# SparkFun_STM32_Thing_Plus.net
KiCad netlist of a schematic drawn in EAGLE
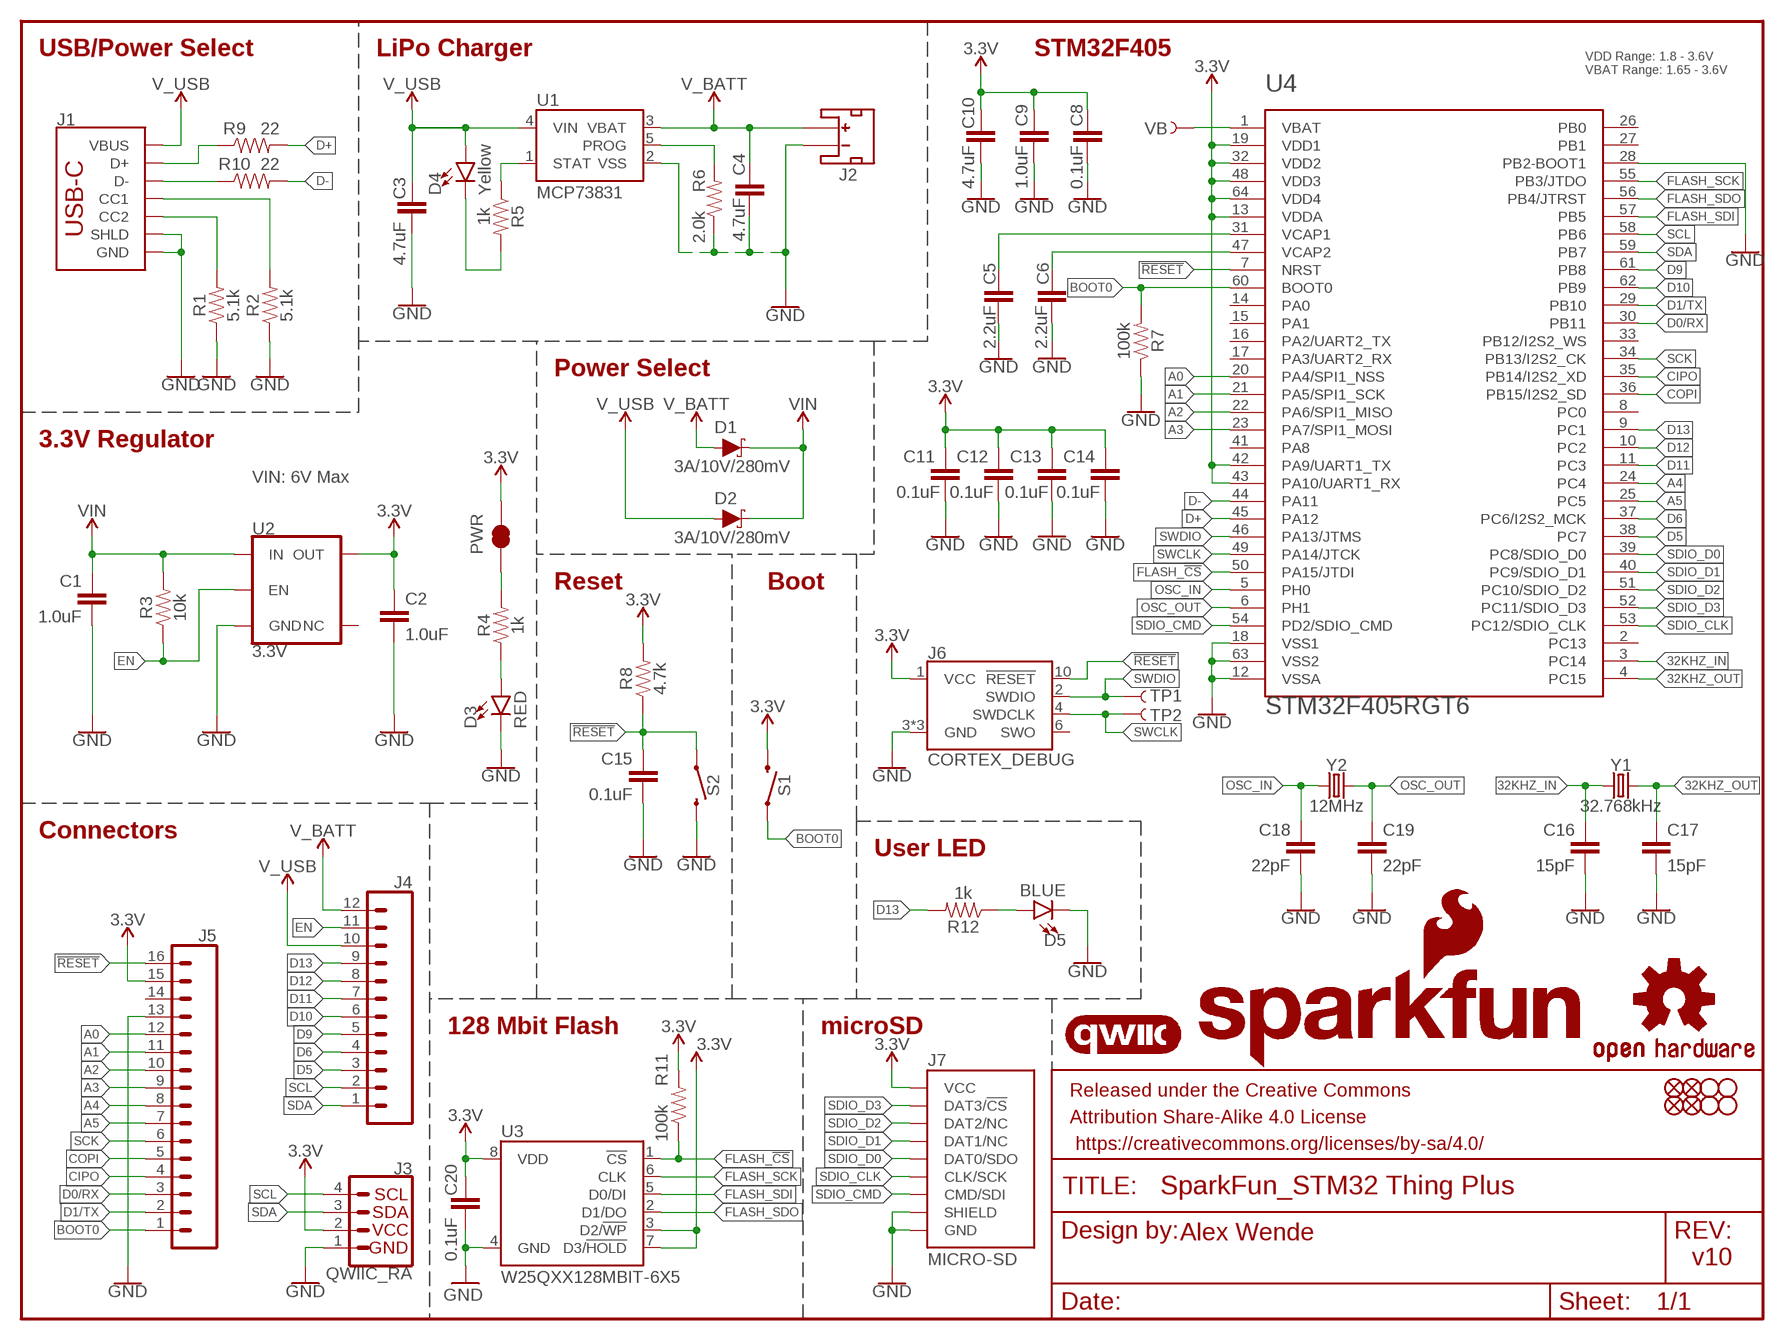
[diagram p0: schematic, sheet 1]

(export (version "E")
  (design (tool "Eeschema 10.0.6"))
  (components
    (comp (ref "C1")
      (value "1.0uF")
      (footprint "eagle-import:0402-TIGHT")
      (libsource (lib "eagle-import") (part "1.0UF-0402T-16V-10%"))
    )
    (comp (ref "C2")
      (value "1.0uF")
      (footprint "eagle-import:0402-TIGHT")
      (libsource (lib "eagle-import") (part "1.0UF-0402T-16V-10%"))
    )
    (comp (ref "C3")
      (value "4.7uF")
      (footprint "eagle-import:0402-TIGHT")
      (libsource (lib "eagle-import") (part "4.7UF-0402_TIGHT-6.3V-20%-X5R"))
    )
    (comp (ref "C4")
      (value "4.7uF")
      (footprint "eagle-import:0402-TIGHT")
      (libsource (lib "eagle-import") (part "4.7UF-0402_TIGHT-6.3V-20%-X5R"))
    )
    (comp (ref "C5")
      (value "2.2uF")
      (footprint "eagle-import:0402-TIGHT")
      (libsource (lib "eagle-import") (part "2.2UF-0402_TIGHT-10V-10%-X5R"))
    )
    (comp (ref "C6")
      (value "2.2uF")
      (footprint "eagle-import:0402-TIGHT")
      (libsource (lib "eagle-import") (part "2.2UF-0402_TIGHT-10V-10%-X5R"))
    )
    (comp (ref "C8")
      (value "0.1uF")
      (footprint "eagle-import:0402-TIGHT")
      (libsource (lib "eagle-import") (part "0.1UF-0402T-10V-10%-X7R"))
    )
    (comp (ref "C9")
      (value "1.0uF")
      (footprint "eagle-import:0402-TIGHT")
      (libsource (lib "eagle-import") (part "1.0UF-0402T-16V-10%"))
    )
    (comp (ref "C10")
      (value "4.7uF")
      (footprint "eagle-import:0402-TIGHT")
      (libsource (lib "eagle-import") (part "4.7UF-0402_TIGHT-6.3V-20%-X5R"))
    )
    (comp (ref "C11")
      (value "0.1uF")
      (footprint "eagle-import:0402-TIGHT")
      (libsource (lib "eagle-import") (part "0.1UF-0402T-10V-10%-X7R"))
    )
    (comp (ref "C12")
      (value "0.1uF")
      (footprint "eagle-import:0402-TIGHT")
      (libsource (lib "eagle-import") (part "0.1UF-0402T-10V-10%-X7R"))
    )
    (comp (ref "C13")
      (value "0.1uF")
      (footprint "eagle-import:0402-TIGHT")
      (libsource (lib "eagle-import") (part "0.1UF-0402T-10V-10%-X7R"))
    )
    (comp (ref "C14")
      (value "0.1uF")
      (footprint "eagle-import:0402-TIGHT")
      (libsource (lib "eagle-import") (part "0.1UF-0402T-10V-10%-X7R"))
    )
    (comp (ref "C15")
      (value "0.1uF")
      (footprint "eagle-import:0402-TIGHT")
      (libsource (lib "eagle-import") (part "0.1UF-0402T-10V-10%-X7R"))
    )
    (comp (ref "C16")
      (value "15pF")
      (footprint "eagle-import:0402-TIGHT")
      (libsource (lib "eagle-import") (part "15PF-0402T-50V-5%"))
    )
    (comp (ref "C17")
      (value "15pF")
      (footprint "eagle-import:0402-TIGHT")
      (libsource (lib "eagle-import") (part "15PF-0402T-50V-5%"))
    )
    (comp (ref "C18")
      (value "22pF")
      (footprint "eagle-import:0402-TIGHT")
      (libsource (lib "eagle-import") (part "22PF-0402T-16V-10%"))
    )
    (comp (ref "C19")
      (value "22pF")
      (footprint "eagle-import:0402-TIGHT")
      (libsource (lib "eagle-import") (part "22PF-0402T-16V-10%"))
    )
    (comp (ref "C20")
      (value "0.1uF")
      (footprint "eagle-import:0402-TIGHT")
      (libsource (lib "eagle-import") (part "0.1UF-0402T-10V-10%-X7R"))
    )
    (comp (ref "D1")
      (value "3A/10V/280mV")
      (footprint "eagle-import:SOD-323")
      (libsource (lib "eagle-import") (part "DIODE-SCHOTTKY-BAT60A"))
    )
    (comp (ref "D2")
      (value "3A/10V/280mV")
      (footprint "eagle-import:SOD-323")
      (libsource (lib "eagle-import") (part "DIODE-SCHOTTKY-BAT60A"))
    )
    (comp (ref "D3")
      (value "RED")
      (footprint "eagle-import:LED-0603")
      (libsource (lib "eagle-import") (part "LED-RED0603"))
    )
    (comp (ref "D4")
      (value "Yellow")
      (footprint "eagle-import:LED-0603")
      (libsource (lib "eagle-import") (part "LED-YELLOW0603"))
    )
    (comp (ref "D5")
      (value "BLUE")
      (footprint "eagle-import:LED-0603")
      (libsource (lib "eagle-import") (part "LED-BLUE0603"))
    )
    (comp (ref "FD1")
      (value "FIDUCIALUFIDUCIAL")
      (footprint "eagle-import:FIDUCIAL-MICRO")
      (libsource (lib "eagle-import") (part "FIDUCIALUFIDUCIAL"))
    )
    (comp (ref "FD2")
      (value "FIDUCIALUFIDUCIAL")
      (footprint "eagle-import:FIDUCIAL-MICRO")
      (libsource (lib "eagle-import") (part "FIDUCIALUFIDUCIAL"))
    )
    (comp (ref "FD3")
      (value "FIDUCIALUFIDUCIAL")
      (footprint "eagle-import:FIDUCIAL-MICRO")
      (libsource (lib "eagle-import") (part "FIDUCIALUFIDUCIAL"))
    )
    (comp (ref "FD4")
      (value "FIDUCIALUFIDUCIAL")
      (footprint "eagle-import:FIDUCIAL-MICRO")
      (libsource (lib "eagle-import") (part "FIDUCIALUFIDUCIAL"))
    )
    (comp (ref "FRAME1")
      (value "FRAME-LETTER")
      (footprint "eagle-import:CREATIVE_COMMONS")
      (libsource (lib "eagle-import") (part "FRAME-LETTER"))
    )
    (comp (ref "H1")
      (value "STAND-OFFTIGHT")
      (footprint "eagle-import:STAND-OFF-TIGHT")
      (libsource (lib "eagle-import") (part "STAND-OFFTIGHT"))
    )
    (comp (ref "H2")
      (value "STAND-OFFTIGHT")
      (footprint "eagle-import:STAND-OFF-TIGHT")
      (libsource (lib "eagle-import") (part "STAND-OFFTIGHT"))
    )
    (comp (ref "H3")
      (value "STAND-OFFTIGHT")
      (footprint "eagle-import:STAND-OFF-TIGHT")
      (libsource (lib "eagle-import") (part "STAND-OFFTIGHT"))
    )
    (comp (ref "H4")
      (value "STAND-OFFTIGHT")
      (footprint "eagle-import:STAND-OFF-TIGHT")
      (libsource (lib "eagle-import") (part "STAND-OFFTIGHT"))
    )
    (comp (ref "J1")
      (value "USB_C_2-LAYER_PADS")
      (footprint "eagle-import:USB-C-16P-2LAYER-PADS")
      (libsource (lib "eagle-import") (part "USB_C_2-LAYER_PADS"))
    )
    (comp (ref "J2")
      (value "JST_2MM_MALE")
      (footprint "eagle-import:JST-2-SMD")
      (libsource (lib "eagle-import") (part "JST_2MM_MALE"))
    )
    (comp (ref "J3")
      (value "QWIIC_RA")
      (footprint "eagle-import:JST04_1MM_RA")
      (libsource (lib "eagle-import") (part "QWIIC_CONNECTORJS-1MM"))
    )
    (comp (ref "J4")
      (value "CONN_12SM_SQ_NO_SILK")
      (footprint "eagle-import:1X12_SM_SQ_NOSILK")
      (libsource (lib "eagle-import") (part "CONN_12SM_SQ_NO_SILK"))
    )
    (comp (ref "J5")
      (value "CONN_161X16_SM_SQ_NOSILK")
      (footprint "eagle-import:1X16_SM_SQ_NOSILK")
      (libsource (lib "eagle-import") (part "CONN_161X16_SM_SQ_NOSILK"))
    )
    (comp (ref "J6")
      (value "CORTEX_DEBUG")
      (footprint "eagle-import:2X5-PTH-1.27MM-NO_SILK")
      (libsource (lib "eagle-import") (part "CORTEX_JTAG_DEBUG_MINIMUM_PTH_NS"))
    )
    (comp (ref "J7")
      (value "MICRO-SD")
      (footprint "eagle-import:MICRO-SD-SOCKET")
      (libsource (lib "eagle-import") (part "MICRO-SD-SDIOPUSH-PUSH"))
    )
    (comp (ref "LOGO1")
      (value "QWIIC_LOGO_5MM")
      (footprint "eagle-import:QWIIC_5MM")
      (libsource (lib "eagle-import") (part "QWIIC_LOGO_5MM"))
    )
    (comp (ref "LOGO2")
      (value "SFE_LOGO_NAME_FLAME.1_INCH")
      (footprint "eagle-import:SFE_LOGO_NAME_FLAME_.1")
      (libsource (lib "eagle-import") (part "SFE_LOGO_NAME_FLAME.1_INCH"))
    )
    (comp (ref "LOGO3")
      (value "OSHW-LOGOS")
      (footprint "eagle-import:OSHW-LOGO-S")
      (libsource (lib "eagle-import") (part "OSHW-LOGOS"))
    )
    (comp (ref "PWR")
      (value "JUMPER-SMT_2_NC_TRACE_NO-SILK")
      (footprint "eagle-import:SMT-JUMPER_2_NC_TRACE_NO-SILK")
      (libsource (lib "eagle-import") (part "JUMPER-SMT_2_NC_TRACE_NO-SILK"))
    )
    (comp (ref "R1")
      (value "5.1k")
      (footprint "eagle-import:0603")
      (libsource (lib "eagle-import") (part "5.1KOHM5.1KOHM-0603-1/10W-1%"))
    )
    (comp (ref "R2")
      (value "5.1k")
      (footprint "eagle-import:0603")
      (libsource (lib "eagle-import") (part "5.1KOHM5.1KOHM-0603-1/10W-1%"))
    )
    (comp (ref "R3")
      (value "10k")
      (footprint "eagle-import:0603")
      (libsource (lib "eagle-import") (part "10KOHM-0603-1/10W-1%"))
    )
    (comp (ref "R4")
      (value "1k")
      (footprint "eagle-import:0402-TIGHT")
      (libsource (lib "eagle-import") (part "1KOHM-0402T-1/16W-1%"))
    )
    (comp (ref "R5")
      (value "1k")
      (footprint "eagle-import:0402-TIGHT")
      (libsource (lib "eagle-import") (part "1KOHM-0402T-1/16W-1%"))
    )
    (comp (ref "R6")
      (value "2.0k")
      (footprint "eagle-import:0603")
      (libsource (lib "eagle-import") (part "2.0KOHM-0603-1/10W-5%"))
    )
    (comp (ref "R7")
      (value "100k")
      (footprint "eagle-import:0402-TIGHT")
      (libsource (lib "eagle-import") (part "100KOHM-0402T-1/16W-1%"))
    )
    (comp (ref "R8")
      (value "4.7k")
      (footprint "eagle-import:0603")
      (libsource (lib "eagle-import") (part "4.7KOHM-0603-1/10W-1%"))
    )
    (comp (ref "R9")
      (value "22")
      (footprint "eagle-import:0603")
      (libsource (lib "eagle-import") (part "22OHM-0603-1/10W-1%"))
    )
    (comp (ref "R10")
      (value "22")
      (footprint "eagle-import:0603")
      (libsource (lib "eagle-import") (part "22OHM-0603-1/10W-1%"))
    )
    (comp (ref "R11")
      (value "100k")
      (footprint "eagle-import:0402-TIGHT")
      (libsource (lib "eagle-import") (part "100KOHM-0402T-1/16W-1%"))
    )
    (comp (ref "R12")
      (value "1k")
      (footprint "eagle-import:0402-TIGHT")
      (libsource (lib "eagle-import") (part "1KOHM-0402T-1/16W-1%"))
    )
    (comp (ref "S1")
      (value "MOMENTARY-SWITCH-SPST-SMD-4.6X2.8MM")
      (footprint "eagle-import:TACTILE_SWITCH_SMD_4.6X2.8MM")
      (libsource (lib "eagle-import") (part "MOMENTARY-SWITCH-SPST-SMD-4.6X2.8MM"))
    )
    (comp (ref "S2")
      (value "MOMENTARY-SWITCH-SPST-SMD-4.6X2.8MM")
      (footprint "eagle-import:TACTILE_SWITCH_SMD_4.6X2.8MM")
      (libsource (lib "eagle-import") (part "MOMENTARY-SWITCH-SPST-SMD-4.6X2.8MM"))
    )
    (comp (ref "TP1")
      (value "TEST-POINT3")
      (footprint "eagle-import:PAD.03X.03")
      (libsource (lib "eagle-import") (part "TEST-POINT3"))
    )
    (comp (ref "TP2")
      (value "TEST-POINT3")
      (footprint "eagle-import:PAD.03X.03")
      (libsource (lib "eagle-import") (part "TEST-POINT3"))
    )
    (comp (ref "U1")
      (value "MCP73831")
      (footprint "eagle-import:SOT23-5")
      (libsource (lib "eagle-import") (part "MCP73831"))
    )
    (comp (ref "U2")
      (value "3.3V")
      (footprint "eagle-import:SOT23-5")
      (libsource (lib "eagle-import") (part "V_REG_AP2112K-3.3V"))
    )
    (comp (ref "U3")
      (value "W25QXX128MBIT-6X5")
      (footprint "eagle-import:WSON-8-6X5")
      (libsource (lib "eagle-import") (part "W25QXX128MBIT-6X5"))
    )
    (comp (ref "U4")
      (value "STM32F405RGT6")
      (footprint "eagle-import:TQFP64")
      (libsource (lib "eagle-import") (part "STM32F405RG"))
    )
    (comp (ref "VB")
      (value "TEST-POINT3")
      (footprint "eagle-import:PAD.03X.03")
      (libsource (lib "eagle-import") (part "TEST-POINT3"))
    )
    (comp (ref "Y1")
      (value "32.768kHz")
      (footprint "eagle-import:CRYSTAL-SMD-3.2X1.5MM")
      (libsource (lib "eagle-import") (part "CRYSTAL-32.768KHZSMD-3.2X1.5"))
    )
    (comp (ref "Y2")
      (value "12MHz")
      (footprint "eagle-import:CRYSTAL-SMD-5X3.2-4PAD")
      (libsource (lib "eagle-import") (part "CRYSTAL-12MHZ{dblquote}"))
    )
  )
  (nets
    (net (code "1") (name "/FLASH_~{CS}") (class "Default")
      (node (ref "R11") (pin "1") (pinfunction "1_1") (pintype "passive"))
      (node (ref "U3") (pin "1") (pinfunction "~{CS}_1") (pintype "bidirectional"))
      (node (ref "U4") (pin "50") (pinfunction "PA15/JTDI_50") (pintype "bidirectional"))
    )
    (net (code "2") (name "/~{RESET}") (class "Default")
      (node (ref "C15") (pin "1") (pinfunction "1_1") (pintype "passive"))
      (node (ref "J5") (pin "16") (pinfunction "16_16") (pintype "passive"))
      (node (ref "J6") (pin "10") (pinfunction "~{RESET}_10") (pintype "bidirectional"))
      (node (ref "R8") (pin "1") (pinfunction "1_1") (pintype "passive"))
      (node (ref "S2") (pin "1") (pinfunction "1_1") (pintype "passive"))
      (node (ref "S2") (pin "2") (pinfunction "1_2") (pintype "passive"))
      (node (ref "U4") (pin "7") (pinfunction "NRST_7") (pintype "bidirectional"))
    )
    (net (code "3") (name "3.3V") (class "Default")
      (node (ref "C10") (pin "1") (pinfunction "1_1") (pintype "passive"))
      (node (ref "C11") (pin "1") (pinfunction "1_1") (pintype "passive"))
      (node (ref "C12") (pin "1") (pinfunction "1_1") (pintype "passive"))
      (node (ref "C13") (pin "1") (pinfunction "1_1") (pintype "passive"))
      (node (ref "C14") (pin "1") (pinfunction "1_1") (pintype "passive"))
      (node (ref "C2") (pin "1") (pinfunction "1_1") (pintype "passive"))
      (node (ref "C20") (pin "1") (pinfunction "1_1") (pintype "passive"))
      (node (ref "C8") (pin "1") (pinfunction "1_1") (pintype "passive"))
      (node (ref "C9") (pin "1") (pinfunction "1_1") (pintype "passive"))
      (node (ref "J3") (pin "2") (pinfunction "2_2") (pintype "power_in"))
      (node (ref "J5") (pin "15") (pinfunction "15_15") (pintype "passive"))
      (node (ref "J6") (pin "1") (pinfunction "VCC_1") (pintype "bidirectional"))
      (node (ref "J7") (pin "VCC") (pinfunction "VCC_VCC") (pintype "bidirectional"))
      (node (ref "PWR") (pin "2") (pinfunction "2_2") (pintype "passive"))
      (node (ref "R11") (pin "2") (pinfunction "2_2") (pintype "passive"))
      (node (ref "R8") (pin "2") (pinfunction "2_2") (pintype "passive"))
      (node (ref "S1") (pin "3") (pinfunction "2_3") (pintype "passive"))
      (node (ref "S1") (pin "4") (pinfunction "2_4") (pintype "passive"))
      (node (ref "U2") (pin "5") (pinfunction "OUT_5") (pintype "passive"))
      (node (ref "U3") (pin "3") (pinfunction "D2/~{WP}_3") (pintype "bidirectional"))
      (node (ref "U3") (pin "7") (pinfunction "D3/~{HOLD}_7") (pintype "bidirectional"))
      (node (ref "U3") (pin "8") (pinfunction "VDD_8") (pintype "bidirectional"))
      (node (ref "U4") (pin "13") (pinfunction "VDDA_13") (pintype "bidirectional"))
      (node (ref "U4") (pin "19") (pinfunction "VDD1_19") (pintype "bidirectional"))
      (node (ref "U4") (pin "32") (pinfunction "VDD2_32") (pintype "bidirectional"))
      (node (ref "U4") (pin "42") (pinfunction "PA9/UART1_TX_42") (pintype "bidirectional"))
      (node (ref "U4") (pin "43") (pinfunction "PA10/UART1_RX_43") (pintype "bidirectional"))
      (node (ref "U4") (pin "48") (pinfunction "VDD3_48") (pintype "bidirectional"))
      (node (ref "U4") (pin "64") (pinfunction "VDD4_64") (pintype "bidirectional"))
    )
    (net (code "4") (name "32KHZ_IN") (class "Default")
      (node (ref "C16") (pin "1") (pinfunction "1_1") (pintype "passive"))
      (node (ref "U4") (pin "3") (pinfunction "PC14_3") (pintype "bidirectional"))
      (node (ref "Y1") (pin "P$1") (pinfunction "1_P$1") (pintype "passive"))
    )
    (net (code "5") (name "32KHZ_OUT") (class "Default")
      (node (ref "C17") (pin "1") (pinfunction "1_1") (pintype "passive"))
      (node (ref "U4") (pin "4") (pinfunction "PC15_4") (pintype "bidirectional"))
      (node (ref "Y1") (pin "P$2") (pinfunction "2_P$2") (pintype "passive"))
    )
    (net (code "6") (name "A0") (class "Default")
      (node (ref "J5") (pin "12") (pinfunction "12_12") (pintype "passive"))
      (node (ref "U4") (pin "20") (pinfunction "PA4/SPI1_NSS_20") (pintype "bidirectional"))
    )
    (net (code "7") (name "A1") (class "Default")
      (node (ref "J5") (pin "11") (pinfunction "11_11") (pintype "passive"))
      (node (ref "U4") (pin "21") (pinfunction "PA5/SPI1_SCK_21") (pintype "bidirectional"))
    )
    (net (code "8") (name "A2") (class "Default")
      (node (ref "J5") (pin "10") (pinfunction "10_10") (pintype "passive"))
      (node (ref "U4") (pin "22") (pinfunction "PA6/SPI1_MISO_22") (pintype "bidirectional"))
    )
    (net (code "9") (name "A3") (class "Default")
      (node (ref "J5") (pin "9") (pinfunction "9_9") (pintype "passive"))
      (node (ref "U4") (pin "23") (pinfunction "PA7/SPI1_MOSI_23") (pintype "bidirectional"))
    )
    (net (code "10") (name "A4") (class "Default")
      (node (ref "J5") (pin "8") (pinfunction "8_8") (pintype "passive"))
      (node (ref "U4") (pin "24") (pinfunction "PC4_24") (pintype "bidirectional"))
    )
    (net (code "11") (name "A5") (class "Default")
      (node (ref "J5") (pin "7") (pinfunction "7_7") (pintype "passive"))
      (node (ref "U4") (pin "25") (pinfunction "PC5_25") (pintype "bidirectional"))
    )
    (net (code "12") (name "BOOT0") (class "Default")
      (node (ref "J5") (pin "1") (pinfunction "1_1") (pintype "passive"))
      (node (ref "R7") (pin "2") (pinfunction "2_2") (pintype "passive"))
      (node (ref "S1") (pin "1") (pinfunction "1_1") (pintype "passive"))
      (node (ref "S1") (pin "2") (pinfunction "1_2") (pintype "passive"))
      (node (ref "U4") (pin "60") (pinfunction "BOOT0_60") (pintype "bidirectional"))
    )
    (net (code "13") (name "CIPO") (class "Default")
      (node (ref "J5") (pin "4") (pinfunction "4_4") (pintype "passive"))
      (node (ref "U4") (pin "35") (pinfunction "PB14/I2S2_XD_35") (pintype "bidirectional"))
    )
    (net (code "14") (name "COPI") (class "Default")
      (node (ref "J5") (pin "5") (pinfunction "5_5") (pintype "passive"))
      (node (ref "U4") (pin "36") (pinfunction "PB15/I2S2_SD_36") (pintype "bidirectional"))
    )
    (net (code "15") (name "D+") (class "Default")
      (node (ref "R9") (pin "2") (pinfunction "2_2") (pintype "passive"))
      (node (ref "U4") (pin "45") (pinfunction "PA12_45") (pintype "bidirectional"))
    )
    (net (code "16") (name "D-") (class "Default")
      (node (ref "R10") (pin "2") (pinfunction "2_2") (pintype "passive"))
      (node (ref "U4") (pin "44") (pinfunction "PA11_44") (pintype "bidirectional"))
    )
    (net (code "17") (name "D0{slash}RX") (class "Default")
      (node (ref "J5") (pin "3") (pinfunction "3_3") (pintype "passive"))
      (node (ref "U4") (pin "30") (pinfunction "PB11_30") (pintype "bidirectional"))
    )
    (net (code "18") (name "D1{slash}TX") (class "Default")
      (node (ref "J5") (pin "2") (pinfunction "2_2") (pintype "passive"))
      (node (ref "U4") (pin "29") (pinfunction "PB10_29") (pintype "bidirectional"))
    )
    (net (code "19") (name "D5") (class "Default")
      (node (ref "J4") (pin "3") (pinfunction "3_3") (pintype "passive"))
      (node (ref "U4") (pin "38") (pinfunction "PC7_38") (pintype "bidirectional"))
    )
    (net (code "20") (name "D6") (class "Default")
      (node (ref "J4") (pin "4") (pinfunction "4_4") (pintype "passive"))
      (node (ref "U4") (pin "37") (pinfunction "PC6/I2S2_MCK_37") (pintype "bidirectional"))
    )
    (net (code "21") (name "D9") (class "Default")
      (node (ref "J4") (pin "5") (pinfunction "5_5") (pintype "passive"))
      (node (ref "U4") (pin "61") (pinfunction "PB8_61") (pintype "bidirectional"))
    )
    (net (code "22") (name "D10") (class "Default")
      (node (ref "J4") (pin "6") (pinfunction "6_6") (pintype "passive"))
      (node (ref "U4") (pin "62") (pinfunction "PB9_62") (pintype "bidirectional"))
    )
    (net (code "23") (name "D11") (class "Default")
      (node (ref "J4") (pin "7") (pinfunction "7_7") (pintype "passive"))
      (node (ref "U4") (pin "11") (pinfunction "PC3_11") (pintype "bidirectional"))
    )
    (net (code "24") (name "D12") (class "Default")
      (node (ref "J4") (pin "8") (pinfunction "8_8") (pintype "passive"))
      (node (ref "U4") (pin "10") (pinfunction "PC2_10") (pintype "bidirectional"))
    )
    (net (code "25") (name "D13") (class "Default")
      (node (ref "J4") (pin "9") (pinfunction "9_9") (pintype "passive"))
      (node (ref "R12") (pin "2") (pinfunction "2_2") (pintype "passive"))
      (node (ref "U4") (pin "9") (pinfunction "PC1_9") (pintype "bidirectional"))
    )
    (net (code "26") (name "EN") (class "Default")
      (node (ref "J4") (pin "11") (pinfunction "11_11") (pintype "passive"))
      (node (ref "R3") (pin "1") (pinfunction "1_1") (pintype "passive"))
      (node (ref "U2") (pin "3") (pinfunction "EN_3") (pintype "input"))
    )
    (net (code "27") (name "FLASH_SCK") (class "Default")
      (node (ref "U3") (pin "6") (pinfunction "CLK_6") (pintype "bidirectional"))
      (node (ref "U4") (pin "55") (pinfunction "PB3/JTDO_55") (pintype "bidirectional"))
    )
    (net (code "28") (name "FLASH_SDI") (class "Default")
      (node (ref "U3") (pin "5") (pinfunction "D0/DI_5") (pintype "bidirectional"))
      (node (ref "U4") (pin "57") (pinfunction "PB5_57") (pintype "bidirectional"))
    )
    (net (code "29") (name "FLASH_SDO") (class "Default")
      (node (ref "U3") (pin "2") (pinfunction "D1/DO_2") (pintype "bidirectional"))
      (node (ref "U4") (pin "56") (pinfunction "PB4/JTRST_56") (pintype "bidirectional"))
    )
    (net (code "30") (name "GND") (class "Default")
      (node (ref "C1") (pin "2") (pinfunction "2_2") (pintype "passive"))
      (node (ref "C10") (pin "2") (pinfunction "2_2") (pintype "passive"))
      (node (ref "C11") (pin "2") (pinfunction "2_2") (pintype "passive"))
      (node (ref "C12") (pin "2") (pinfunction "2_2") (pintype "passive"))
      (node (ref "C13") (pin "2") (pinfunction "2_2") (pintype "passive"))
      (node (ref "C14") (pin "2") (pinfunction "2_2") (pintype "passive"))
      (node (ref "C15") (pin "2") (pinfunction "2_2") (pintype "passive"))
      (node (ref "C16") (pin "2") (pinfunction "2_2") (pintype "passive"))
      (node (ref "C17") (pin "2") (pinfunction "2_2") (pintype "passive"))
      (node (ref "C18") (pin "2") (pinfunction "2_2") (pintype "passive"))
      (node (ref "C19") (pin "2") (pinfunction "2_2") (pintype "passive"))
      (node (ref "C2") (pin "2") (pinfunction "2_2") (pintype "passive"))
      (node (ref "C20") (pin "2") (pinfunction "2_2") (pintype "passive"))
      (node (ref "C3") (pin "2") (pinfunction "2_2") (pintype "passive"))
      (node (ref "C4") (pin "2") (pinfunction "2_2") (pintype "passive"))
      (node (ref "C5") (pin "2") (pinfunction "2_2") (pintype "passive"))
      (node (ref "C6") (pin "2") (pinfunction "2_2") (pintype "passive"))
      (node (ref "C8") (pin "2") (pinfunction "2_2") (pintype "passive"))
      (node (ref "C9") (pin "2") (pinfunction "2_2") (pintype "passive"))
      (node (ref "D3") (pin "C") (pinfunction "C_C") (pintype "passive"))
      (node (ref "D5") (pin "C") (pinfunction "C_C") (pintype "passive"))
      (node (ref "J1") (pin "GND") (pinfunction "GND_GND") (pintype "bidirectional"))
      (node (ref "J1") (pin "GND2") (pinfunction "GND_GND2") (pintype "bidirectional"))
      (node (ref "J1") (pin "SHLD1") (pinfunction "SHLD_SHLD1") (pintype "bidirectional"))
      (node (ref "J1") (pin "SHLD2") (pinfunction "SHLD_SHLD2") (pintype "bidirectional"))
      (node (ref "J1") (pin "SHLD3") (pinfunction "SHLD_SHLD3") (pintype "bidirectional"))
      (node (ref "J1") (pin "SHLD4") (pinfunction "SHLD_SHLD4") (pintype "bidirectional"))
      (node (ref "J2") (pin "1") (pinfunction "-_1") (pintype "bidirectional"))
      (node (ref "J3") (pin "1") (pinfunction "1_1") (pintype "power_in"))
      (node (ref "J5") (pin "13") (pinfunction "13_13") (pintype "passive"))
      (node (ref "J6") (pin "3") (pinfunction "GND_3") (pintype "bidirectional"))
      (node (ref "J6") (pin "5") (pinfunction "GND_5") (pintype "bidirectional"))
      (node (ref "J6") (pin "9") (pinfunction "GND_9") (pintype "bidirectional"))
      (node (ref "J7") (pin "CD1") (pinfunction "SHIELD_CD1") (pintype "bidirectional"))
      (node (ref "J7") (pin "GND") (pinfunction "GND_GND") (pintype "bidirectional"))
      (node (ref "J7") (pin "GND1") (pinfunction "GND_GND1") (pintype "bidirectional"))
      (node (ref "J7") (pin "GND3") (pinfunction "GND_GND3") (pintype "bidirectional"))
      (node (ref "R1") (pin "1") (pinfunction "1_1") (pintype "passive"))
      (node (ref "R2") (pin "1") (pinfunction "1_1") (pintype "passive"))
      (node (ref "R6") (pin "1") (pinfunction "1_1") (pintype "passive"))
      (node (ref "R7") (pin "1") (pinfunction "1_1") (pintype "passive"))
      (node (ref "S2") (pin "3") (pinfunction "2_3") (pintype "passive"))
      (node (ref "S2") (pin "4") (pinfunction "2_4") (pintype "passive"))
      (node (ref "U1") (pin "2") (pinfunction "VSS_2") (pintype "power_in"))
      (node (ref "U2") (pin "2") (pinfunction "GND_2") (pintype "input"))
      (node (ref "U3") (pin "4") (pinfunction "GND_4") (pintype "bidirectional"))
      (node (ref "U4") (pin "12") (pinfunction "VSSA_12") (pintype "bidirectional"))
      (node (ref "U4") (pin "18") (pinfunction "VSS1_18") (pintype "bidirectional"))
      (node (ref "U4") (pin "28") (pinfunction "PB2-BOOT1_28") (pintype "bidirectional"))
      (node (ref "U4") (pin "63") (pinfunction "VSS2_63") (pintype "bidirectional"))
    )
    (net (code "31") (name "Net-(D3-PadA)") (class "Default")
      (node (ref "D3") (pin "A") (pinfunction "A_A") (pintype "passive"))
      (node (ref "R4") (pin "1") (pinfunction "1_1") (pintype "passive"))
    )
    (net (code "32") (name "Net-(D4-PadC)") (class "Default")
      (node (ref "D4") (pin "C") (pinfunction "C_C") (pintype "passive"))
      (node (ref "R5") (pin "2") (pinfunction "2_2") (pintype "passive"))
    )
    (net (code "33") (name "Net-(D5-PadA)") (class "Default")
      (node (ref "D5") (pin "A") (pinfunction "A_A") (pintype "passive"))
      (node (ref "R12") (pin "1") (pinfunction "1_1") (pintype "passive"))
    )
    (net (code "34") (name "Net-(J1-CC1)") (class "Default")
      (node (ref "J1") (pin "A5") (pinfunction "CC1_A5") (pintype "bidirectional"))
      (node (ref "R2") (pin "2") (pinfunction "2_2") (pintype "passive"))
    )
    (net (code "35") (name "Net-(J1-CC2)") (class "Default")
      (node (ref "J1") (pin "B5") (pinfunction "CC2_B5") (pintype "bidirectional"))
      (node (ref "R1") (pin "2") (pinfunction "2_2") (pintype "passive"))
    )
    (net (code "36") (name "Net-(J1-D+-PadA6)") (class "Default")
      (node (ref "J1") (pin "A6") (pinfunction "D+_A6") (pintype "bidirectional"))
      (node (ref "J1") (pin "B6") (pinfunction "D+_B6") (pintype "bidirectional"))
      (node (ref "R9") (pin "1") (pinfunction "1_1") (pintype "passive"))
    )
    (net (code "37") (name "Net-(J1-D--PadA7)") (class "Default")
      (node (ref "J1") (pin "A7") (pinfunction "D-_A7") (pintype "bidirectional"))
      (node (ref "J1") (pin "B7") (pinfunction "D-_B7") (pintype "bidirectional"))
      (node (ref "R10") (pin "1") (pinfunction "1_1") (pintype "passive"))
    )
    (net (code "38") (name "Net-(PWR-Pad1)") (class "Default")
      (node (ref "PWR") (pin "1") (pinfunction "1_1") (pintype "passive"))
      (node (ref "R4") (pin "2") (pinfunction "2_2") (pintype "passive"))
    )
    (net (code "39") (name "Net-(U1-PROG)") (class "Default")
      (node (ref "R6") (pin "2") (pinfunction "2_2") (pintype "passive"))
      (node (ref "U1") (pin "5") (pinfunction "PROG_5") (pintype "input"))
    )
    (net (code "40") (name "Net-(U1-STAT)") (class "Default")
      (node (ref "R5") (pin "1") (pinfunction "1_1") (pintype "passive"))
      (node (ref "U1") (pin "1") (pinfunction "STAT_1") (pintype "output"))
    )
    (net (code "41") (name "Net-(U4-VBAT)") (class "Default")
      (node (ref "U4") (pin "1") (pinfunction "VBAT_1") (pintype "bidirectional"))
      (node (ref "VB") (pin "P$1") (pinfunction "1_P$1") (pintype "bidirectional"))
    )
    (net (code "42") (name "Net-(U4-VCAP1)") (class "Default")
      (node (ref "C5") (pin "1") (pinfunction "1_1") (pintype "passive"))
      (node (ref "U4") (pin "31") (pinfunction "VCAP1_31") (pintype "bidirectional"))
    )
    (net (code "43") (name "Net-(U4-VCAP2)") (class "Default")
      (node (ref "C6") (pin "1") (pinfunction "1_1") (pintype "passive"))
      (node (ref "U4") (pin "47") (pinfunction "VCAP2_47") (pintype "bidirectional"))
    )
    (net (code "44") (name "OSC_IN") (class "Default")
      (node (ref "C18") (pin "1") (pinfunction "1_1") (pintype "passive"))
      (node (ref "U4") (pin "5") (pinfunction "PH0_5") (pintype "bidirectional"))
      (node (ref "Y2") (pin "1") (pinfunction "1_1") (pintype "passive"))
    )
    (net (code "45") (name "OSC_OUT") (class "Default")
      (node (ref "C19") (pin "1") (pinfunction "1_1") (pintype "passive"))
      (node (ref "U4") (pin "6") (pinfunction "PH1_6") (pintype "bidirectional"))
      (node (ref "Y2") (pin "3") (pinfunction "2_3") (pintype "passive"))
    )
    (net (code "46") (name "SCK") (class "Default")
      (node (ref "J5") (pin "6") (pinfunction "6_6") (pintype "passive"))
      (node (ref "U4") (pin "34") (pinfunction "PB13/I2S2_CK_34") (pintype "bidirectional"))
    )
    (net (code "47") (name "SCL") (class "Default")
      (node (ref "J3") (pin "4") (pinfunction "4_4") (pintype "passive"))
      (node (ref "J4") (pin "2") (pinfunction "2_2") (pintype "passive"))
      (node (ref "U4") (pin "58") (pinfunction "PB6_58") (pintype "bidirectional"))
    )
    (net (code "48") (name "SDA") (class "Default")
      (node (ref "J3") (pin "3") (pinfunction "3_3") (pintype "passive"))
      (node (ref "J4") (pin "1") (pinfunction "1_1") (pintype "passive"))
      (node (ref "U4") (pin "59") (pinfunction "PB7_59") (pintype "bidirectional"))
    )
    (net (code "49") (name "SDIO_CLK") (class "Default")
      (node (ref "J7") (pin "SCLK") (pinfunction "CLK/SCK_SCLK") (pintype "bidirectional"))
      (node (ref "U4") (pin "53") (pinfunction "PC12/SDIO_CLK_53") (pintype "bidirectional"))
    )
    (net (code "50") (name "SDIO_CMD") (class "Default")
      (node (ref "J7") (pin "DI/CMD") (pinfunction "CMD/SDI_DI/CMD") (pintype "bidirectional"))
      (node (ref "U4") (pin "54") (pinfunction "PD2/SDIO_CMD_54") (pintype "bidirectional"))
    )
    (net (code "51") (name "SDIO_D0") (class "Default")
      (node (ref "J7") (pin "DO/DAT0") (pinfunction "DAT0/SDO_DO/DAT0") (pintype "bidirectional"))
      (node (ref "U4") (pin "39") (pinfunction "PC8/SDIO_D0_39") (pintype "bidirectional"))
    )
    (net (code "52") (name "SDIO_D1") (class "Default")
      (node (ref "J7") (pin "DAT1") (pinfunction "DAT1/NC_DAT1") (pintype "bidirectional"))
      (node (ref "U4") (pin "40") (pinfunction "PC9/SDIO_D1_40") (pintype "bidirectional"))
    )
    (net (code "53") (name "SDIO_D2") (class "Default")
      (node (ref "J7") (pin "DAT2") (pinfunction "DAT2/NC_DAT2") (pintype "bidirectional"))
      (node (ref "U4") (pin "51") (pinfunction "PC10/SDIO_D2_51") (pintype "bidirectional"))
    )
    (net (code "54") (name "SDIO_D3") (class "Default")
      (node (ref "J7") (pin "CS/DAT3") (pinfunction "DAT3/~{CS}_CS/DAT3") (pintype "bidirectional"))
      (node (ref "U4") (pin "52") (pinfunction "PC11/SDIO_D3_52") (pintype "bidirectional"))
    )
    (net (code "55") (name "SWCLK") (class "Default")
      (node (ref "J6") (pin "4") (pinfunction "SWDCLK_4") (pintype "bidirectional"))
      (node (ref "TP2") (pin "P$1") (pinfunction "1_P$1") (pintype "bidirectional"))
      (node (ref "U4") (pin "49") (pinfunction "PA14/JTCK_49") (pintype "bidirectional"))
    )
    (net (code "56") (name "SWDIO") (class "Default")
      (node (ref "J6") (pin "2") (pinfunction "SWDIO_2") (pintype "bidirectional"))
      (node (ref "TP1") (pin "P$1") (pinfunction "1_P$1") (pintype "bidirectional"))
      (node (ref "U4") (pin "46") (pinfunction "PA13/JTMS_46") (pintype "bidirectional"))
    )
    (net (code "57") (name "VIN") (class "Default")
      (node (ref "C1") (pin "1") (pinfunction "1_1") (pintype "passive"))
      (node (ref "D1") (pin "C") (pinfunction "C_C") (pintype "passive"))
      (node (ref "D2") (pin "C") (pinfunction "C_C") (pintype "passive"))
      (node (ref "R3") (pin "2") (pinfunction "2_2") (pintype "passive"))
      (node (ref "U2") (pin "1") (pinfunction "IN_1") (pintype "input"))
    )
    (net (code "58") (name "V_BATT") (class "Default")
      (node (ref "C4") (pin "1") (pinfunction "1_1") (pintype "passive"))
      (node (ref "D1") (pin "A") (pinfunction "A_A") (pintype "passive"))
      (node (ref "J2") (pin "2") (pinfunction "+_2") (pintype "bidirectional"))
      (node (ref "J4") (pin "12") (pinfunction "12_12") (pintype "passive"))
      (node (ref "U1") (pin "3") (pinfunction "VBAT_3") (pintype "power_in"))
    )
    (net (code "59") (name "V_USB") (class "Default")
      (node (ref "C3") (pin "1") (pinfunction "1_1") (pintype "passive"))
      (node (ref "D2") (pin "A") (pinfunction "A_A") (pintype "passive"))
      (node (ref "D4") (pin "A") (pinfunction "A_A") (pintype "passive"))
      (node (ref "J1") (pin "VBUS1") (pinfunction "VBUS_VBUS1") (pintype "bidirectional"))
      (node (ref "J1") (pin "VBUS2") (pinfunction "VBUS_VBUS2") (pintype "bidirectional"))
      (node (ref "J4") (pin "10") (pinfunction "10_10") (pintype "passive"))
      (node (ref "U1") (pin "4") (pinfunction "VIN_4") (pintype "power_in"))
    )
    (net (code "60") (name "unconnected-(J2-PAD1-PadNC1)") (class "Default")
      (node (ref "J2") (pin "NC1") (pinfunction "PAD1_NC1") (pintype "bidirectional"))
    )
    (net (code "61") (name "unconnected-(J2-PAD2-PadNC2)") (class "Default")
      (node (ref "J2") (pin "NC2") (pinfunction "PAD2_NC2") (pintype "bidirectional"))
    )
    (net (code "62") (name "unconnected-(J5-Pad14)") (class "Default")
      (node (ref "J5") (pin "14") (pinfunction "14_14") (pintype "passive"))
    )
    (net (code "63") (name "unconnected-(J6-SWO-Pad6)") (class "Default")
      (node (ref "J6") (pin "6") (pinfunction "SWO_6") (pintype "bidirectional"))
    )
    (net (code "64") (name "unconnected-(U2-NC-Pad4)") (class "Default")
      (node (ref "U2") (pin "4") (pinfunction "NC_4") (pintype "no_connect"))
    )
    (net (code "65") (name "unconnected-(U4-PA0-Pad14)") (class "Default")
      (node (ref "U4") (pin "14") (pinfunction "PA0_14") (pintype "bidirectional"))
    )
    (net (code "66") (name "unconnected-(U4-PA1-Pad15)") (class "Default")
      (node (ref "U4") (pin "15") (pinfunction "PA1_15") (pintype "bidirectional"))
    )
    (net (code "67") (name "unconnected-(U4-PA2{slash}UART2_TX-Pad16)") (class "Default")
      (node (ref "U4") (pin "16") (pinfunction "PA2/UART2_TX_16") (pintype "bidirectional"))
    )
    (net (code "68") (name "unconnected-(U4-PA3{slash}UART2_RX-Pad17)") (class "Default")
      (node (ref "U4") (pin "17") (pinfunction "PA3/UART2_RX_17") (pintype "bidirectional"))
    )
    (net (code "69") (name "unconnected-(U4-PA8-Pad41)") (class "Default")
      (node (ref "U4") (pin "41") (pinfunction "PA8_41") (pintype "bidirectional"))
    )
    (net (code "70") (name "unconnected-(U4-PB0-Pad26)") (class "Default")
      (node (ref "U4") (pin "26") (pinfunction "PB0_26") (pintype "bidirectional"))
    )
    (net (code "71") (name "unconnected-(U4-PB1-Pad27)") (class "Default")
      (node (ref "U4") (pin "27") (pinfunction "PB1_27") (pintype "bidirectional"))
    )
    (net (code "72") (name "unconnected-(U4-PB12{slash}I2S2_WS-Pad33)") (class "Default")
      (node (ref "U4") (pin "33") (pinfunction "PB12/I2S2_WS_33") (pintype "bidirectional"))
    )
    (net (code "73") (name "unconnected-(U4-PC0-Pad8)") (class "Default")
      (node (ref "U4") (pin "8") (pinfunction "PC0_8") (pintype "bidirectional"))
    )
    (net (code "74") (name "unconnected-(U4-PC13-Pad2)") (class "Default")
      (node (ref "U4") (pin "2") (pinfunction "PC13_2") (pintype "bidirectional"))
    )
  )
)
